# 16.net
KiCad netlist of a schematic drawn in EasyEDA Pro
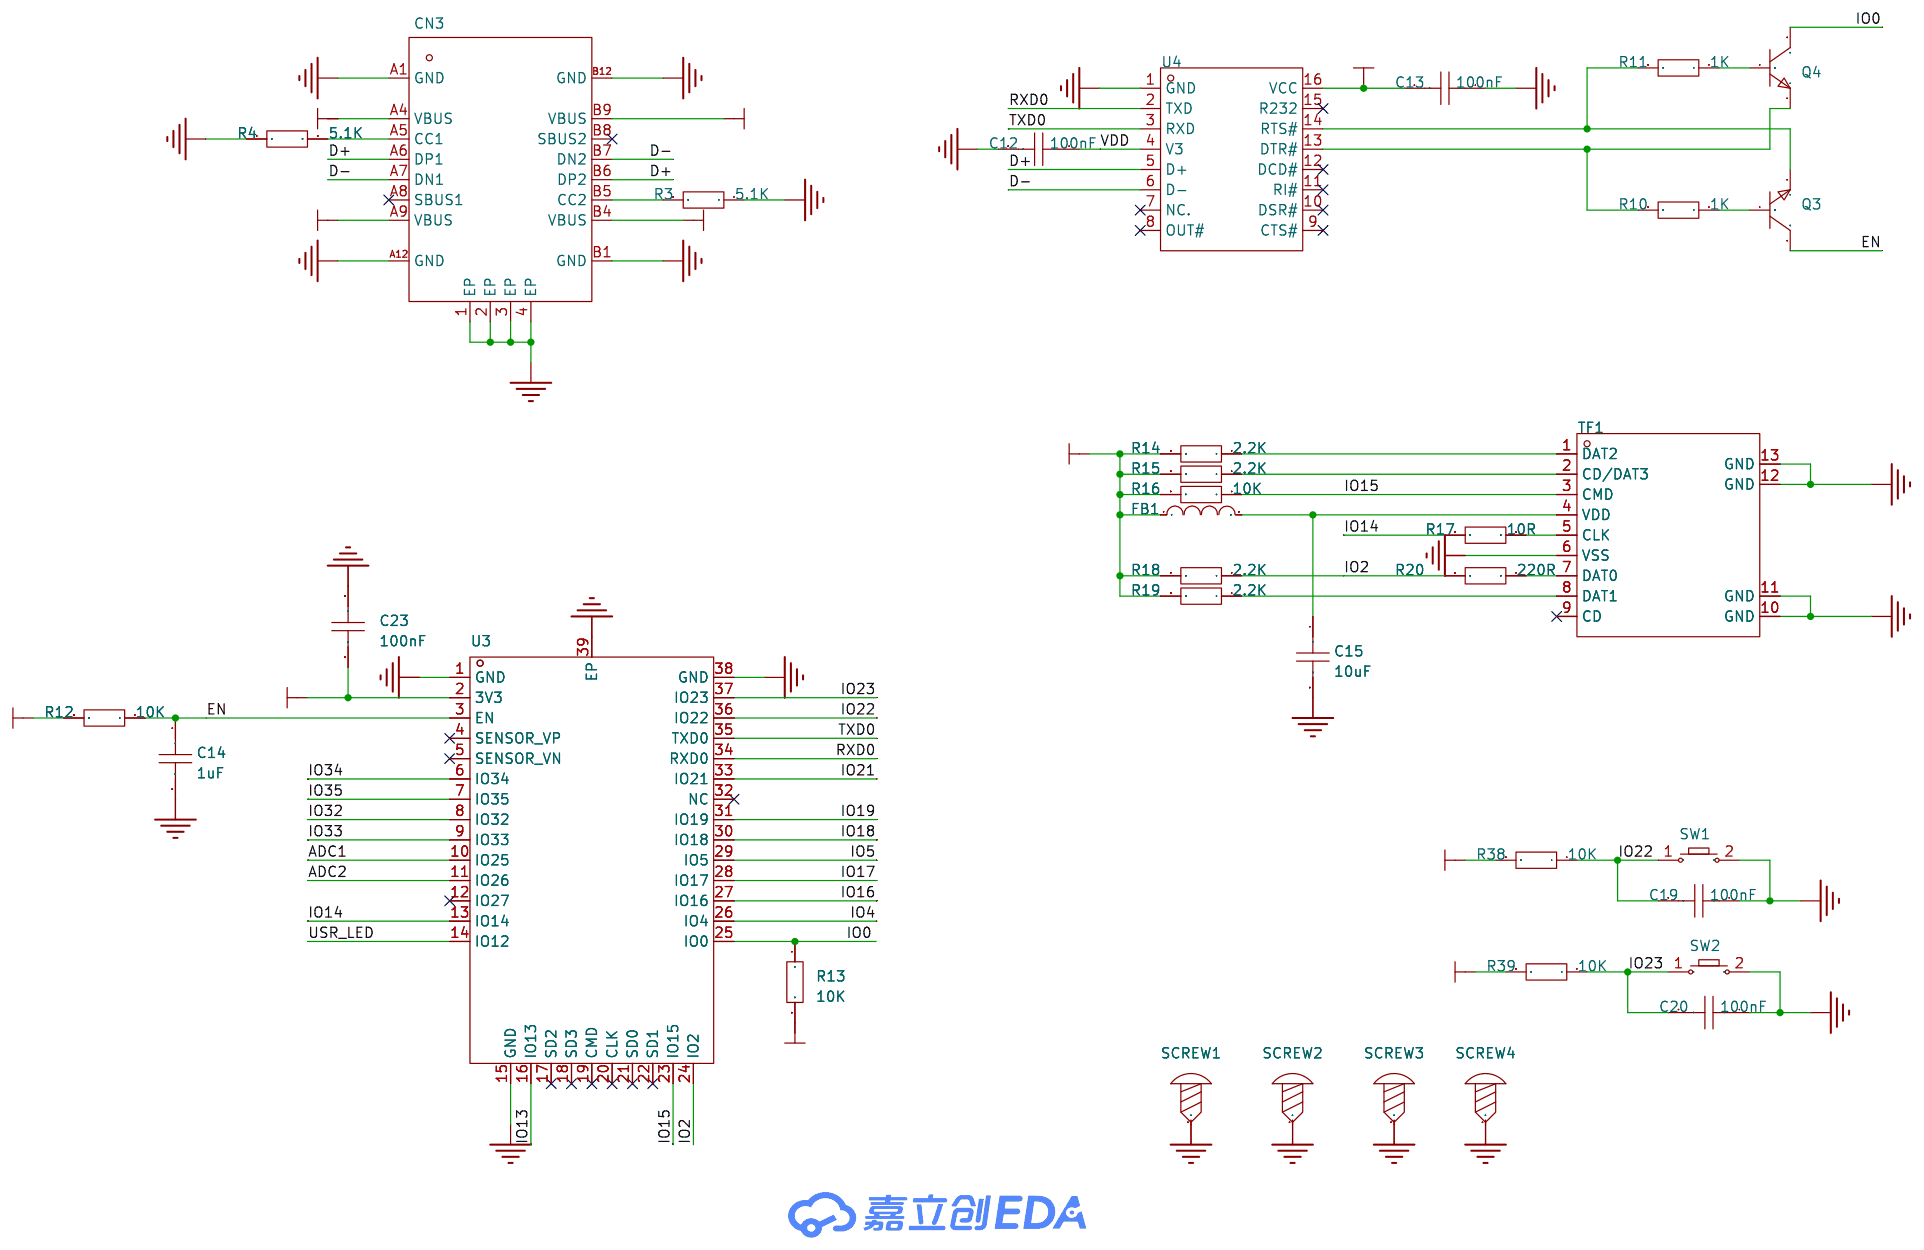
[diagram p0: ESP32]
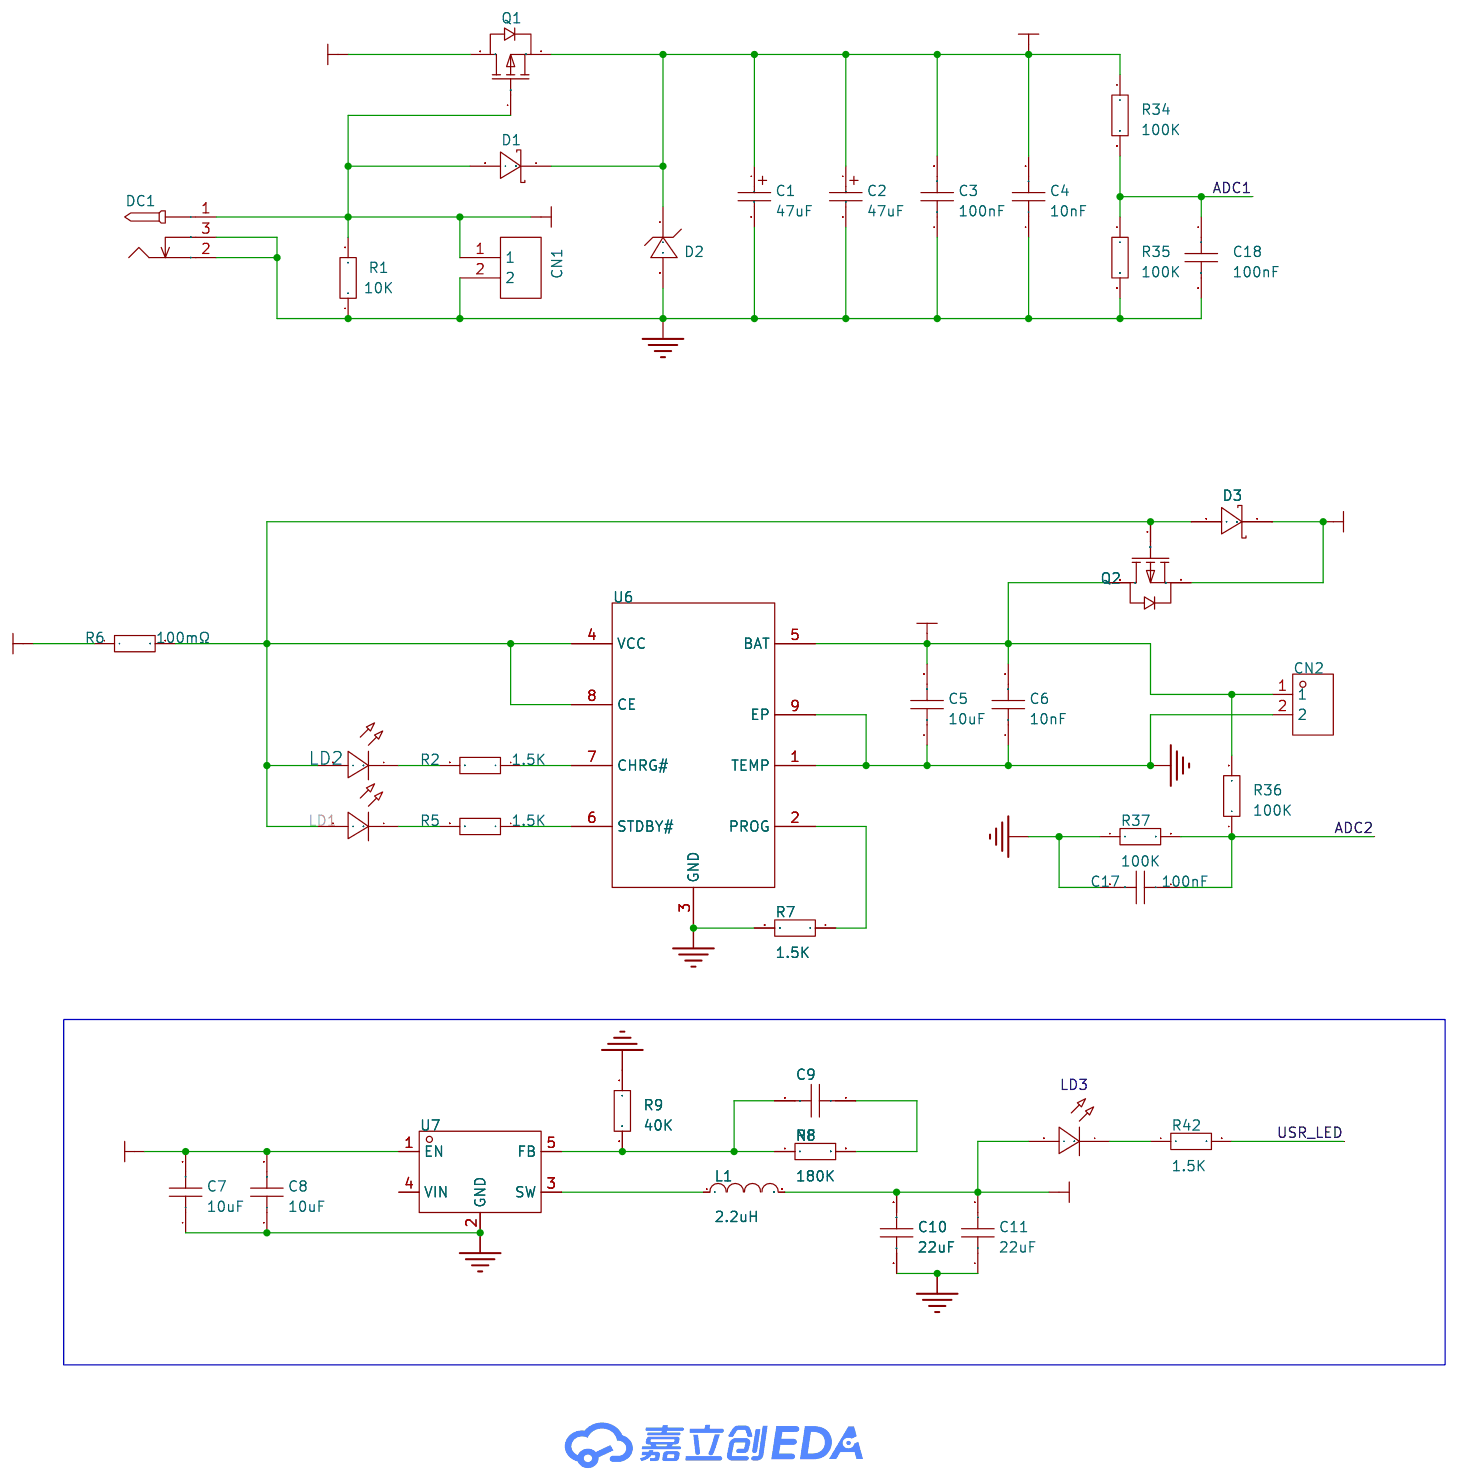
[diagram p1: DC]
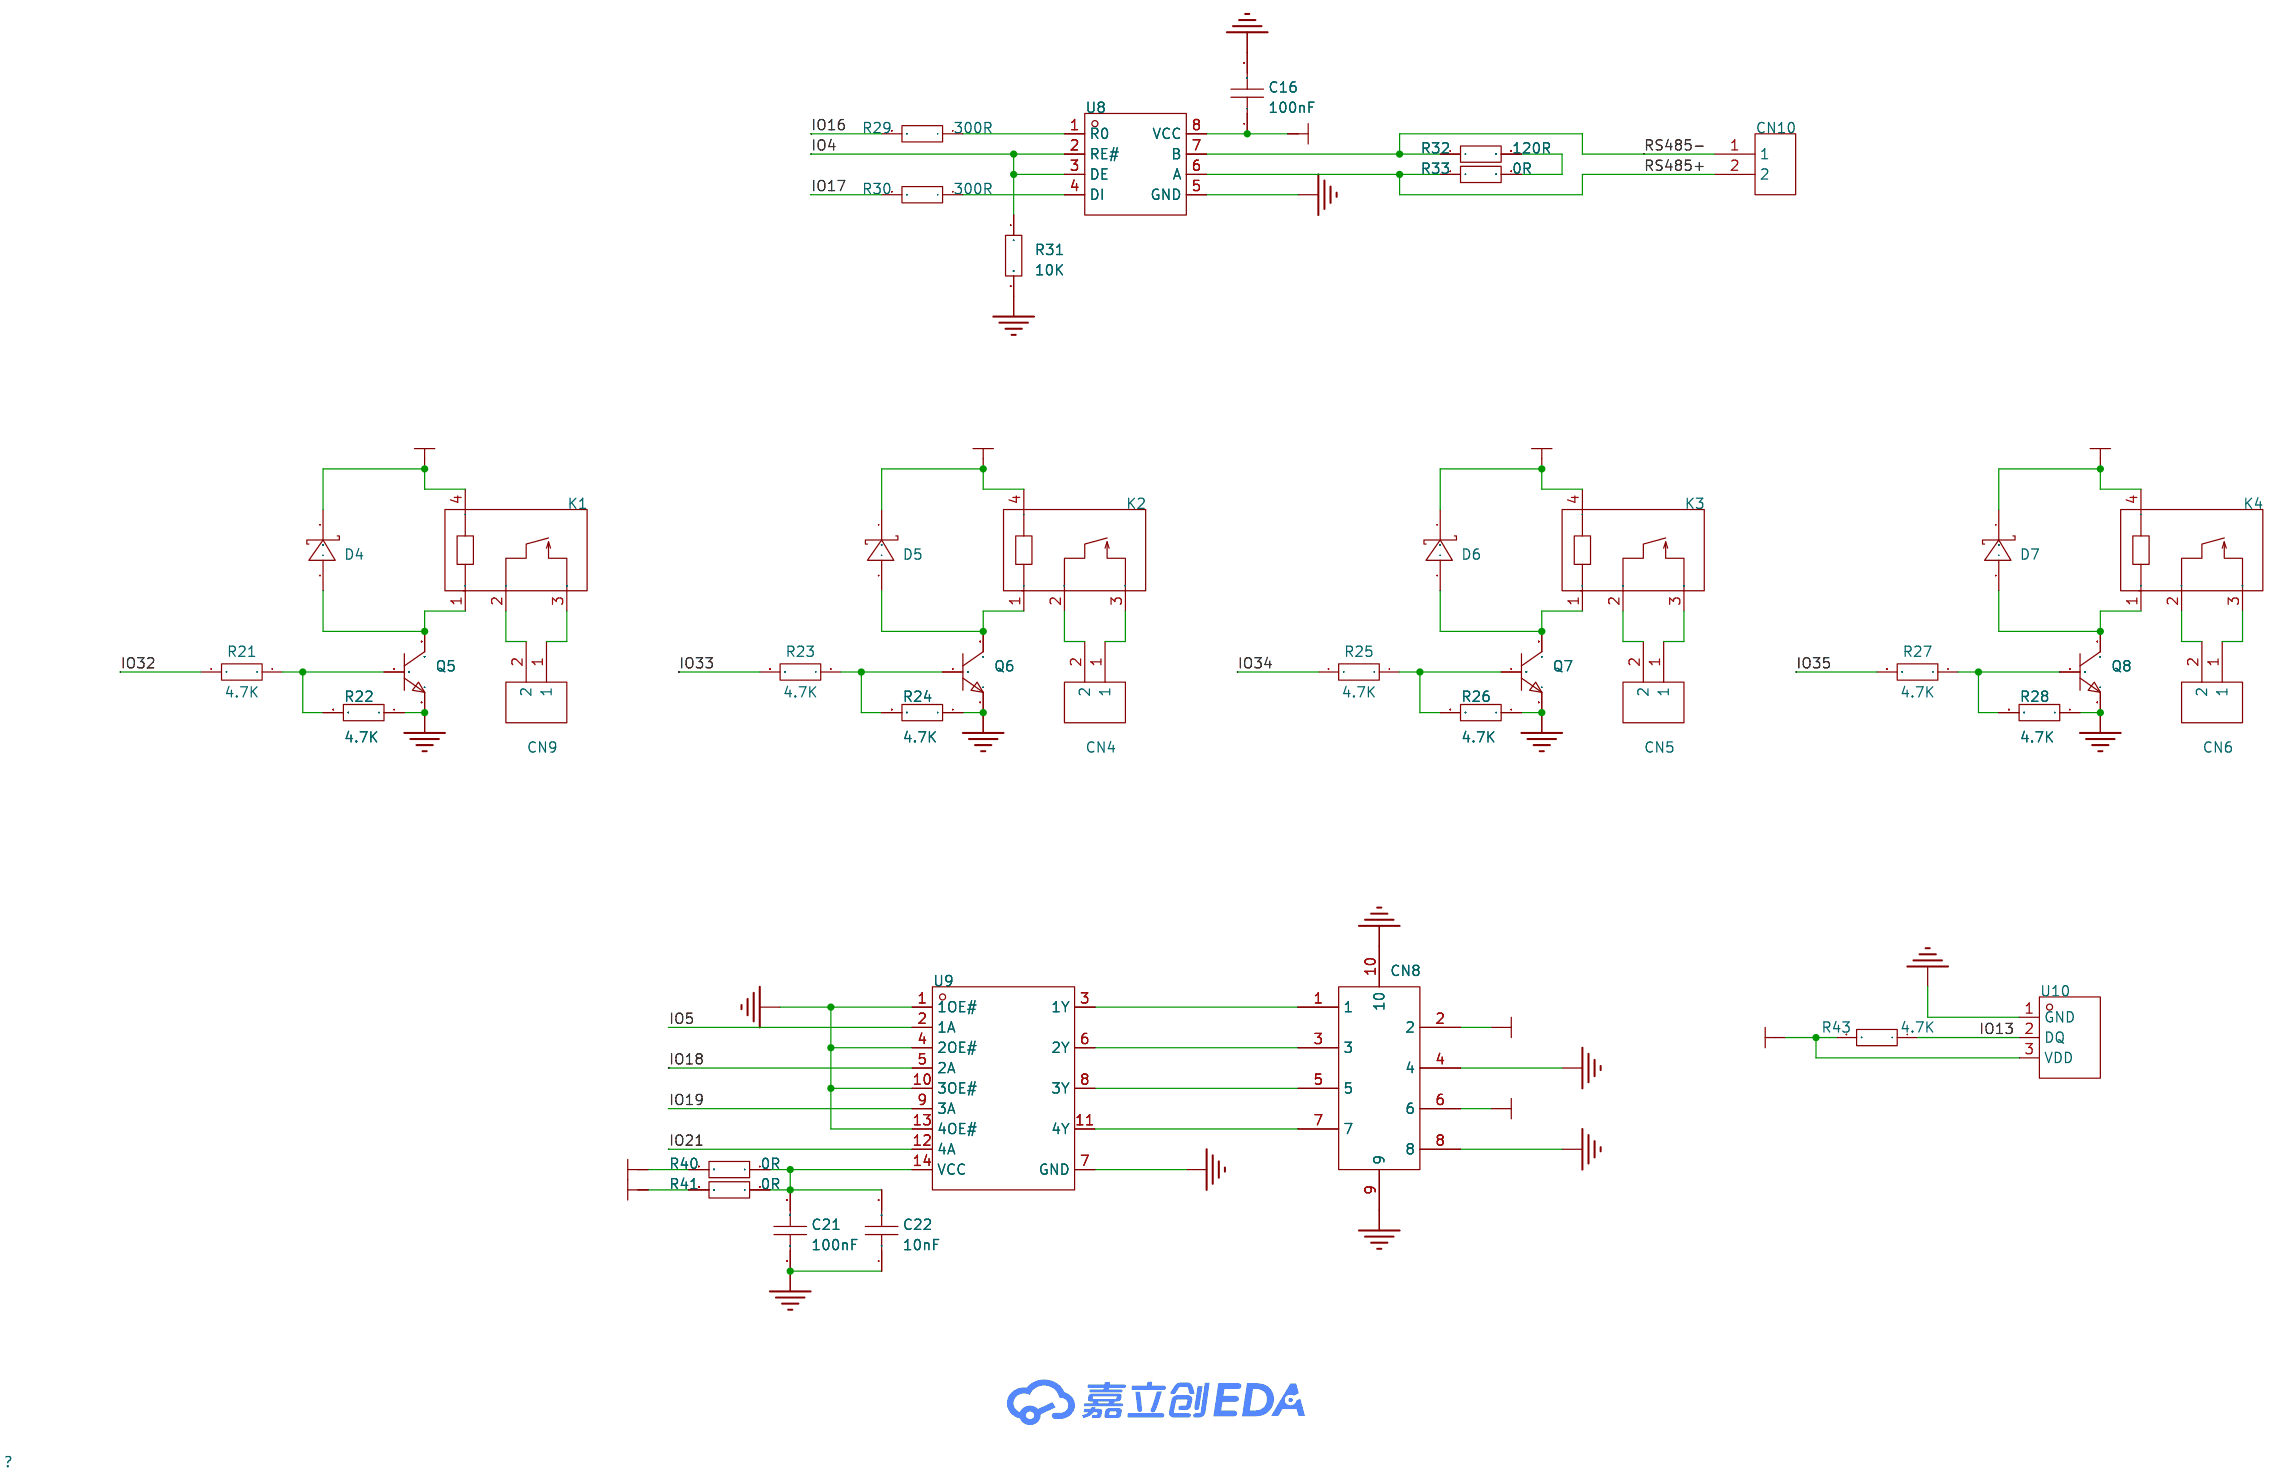
[diagram p2: RELAY]

(export (version "E")
  (design (tool "Eeschema 10.0.6"))
  (components
    (comp (ref "C12")
      (value "100nF")
      (footprint "easyedapro:C0805")
      (libsource (lib "easyedapro") (part "CapAcitance"))
    )
    (comp (ref "C13")
      (value "100nF")
      (footprint "easyedapro:C0805")
      (libsource (lib "easyedapro") (part "CapAcitance"))
    )
    (comp (ref "C14")
      (value "1uF")
      (footprint "easyedapro:C0805")
      (libsource (lib "easyedapro") (part "CapAcitance"))
    )
    (comp (ref "C15")
      (value "10uF")
      (footprint "easyedapro:C0805")
      (libsource (lib "easyedapro") (part "CapAcitance"))
    )
    (comp (ref "C19")
      (value "100nF")
      (footprint "easyedapro:C0805")
      (libsource (lib "easyedapro") (part "CapAcitance"))
    )
    (comp (ref "C20")
      (value "100nF")
      (footprint "easyedapro:C0805")
      (libsource (lib "easyedapro") (part "CapAcitance"))
    )
    (comp (ref "C23")
      (value "100nF")
      (footprint "easyedapro:C0805")
      (libsource (lib "easyedapro") (part "CapAcitance"))
    )
    (comp (ref "CN3")
      (value "~")
      (footprint "easyedapro:USB_TYPE-C-16P")
      (libsource (lib "easyedapro") (part "USB_TYPE-C-16P"))
    )
    (comp (ref "FB1")
      (value "10uH")
      (footprint "easyedapro:L0805")
      (libsource (lib "easyedapro") (part "SDFL2012S100KTF"))
    )
    (comp (ref "Q3")
      (value "SS8050")
      (footprint "easyedapro:SOT-23-3_L2.9-W1.3-P1.90-LS2.4-BR")
      (fields (field (name "Manufacturer") "宏迦橙"))
      (libsource (lib "easyedapro") (part "SS8050_C7420370"))
    )
    (comp (ref "Q4")
      (value "SS8050")
      (footprint "easyedapro:SOT-23-3_L2.9-W1.3-P1.90-LS2.4-BR")
      (fields (field (name "Manufacturer") "宏迦橙"))
      (libsource (lib "easyedapro") (part "SS8050_C7420370"))
    )
    (comp (ref "R3") (value "5.1K") (footprint "easyedapro:R0805") (libsource (lib "easyedapro") (part "电阻")))
    (comp (ref "R4") (value "5.1K") (footprint "easyedapro:R0805") (libsource (lib "easyedapro") (part "电阻")))
    (comp (ref "R10") (value "1K") (footprint "easyedapro:R0805") (libsource (lib "easyedapro") (part "电阻")))
    (comp (ref "R11") (value "1K") (footprint "easyedapro:R0805") (libsource (lib "easyedapro") (part "电阻")))
    (comp (ref "R12") (value "10K") (footprint "easyedapro:R0805") (libsource (lib "easyedapro") (part "电阻")))
    (comp (ref "R13") (value "10K") (footprint "easyedapro:R0805") (libsource (lib "easyedapro") (part "电阻")))
    (comp (ref "R14")
      (value "2.2K")
      (footprint "easyedapro:R0805")
      (libsource (lib "easyedapro") (part "电阻"))
    )
    (comp (ref "R15")
      (value "2.2K")
      (footprint "easyedapro:R0805")
      (libsource (lib "easyedapro") (part "电阻"))
    )
    (comp (ref "R16") (value "10K") (footprint "easyedapro:R0805") (libsource (lib "easyedapro") (part "电阻")))
    (comp (ref "R17") (value "10R") (footprint "easyedapro:R0805") (libsource (lib "easyedapro") (part "电阻")))
    (comp (ref "R18")
      (value "2.2K")
      (footprint "easyedapro:R0805")
      (libsource (lib "easyedapro") (part "电阻"))
    )
    (comp (ref "R19")
      (value "2.2K")
      (footprint "easyedapro:R0805")
      (libsource (lib "easyedapro") (part "电阻"))
    )
    (comp (ref "R20")
      (value "220R")
      (footprint "easyedapro:R0805")
      (libsource (lib "easyedapro") (part "电阻"))
    )
    (comp (ref "R38") (value "10K") (footprint "easyedapro:R0805") (libsource (lib "easyedapro") (part "电阻")))
    (comp (ref "R39") (value "10K") (footprint "easyedapro:R0805") (libsource (lib "easyedapro") (part "电阻")))
    (comp (ref "SCREW1")
      (value "~")
      (footprint "easyedapro:M2螺丝")
      (libsource (lib "easyedapro") (part "螺丝孔"))
    )
    (comp (ref "SCREW2")
      (value "~")
      (footprint "easyedapro:M2螺丝")
      (libsource (lib "easyedapro") (part "螺丝孔"))
    )
    (comp (ref "SCREW3")
      (value "~")
      (footprint "easyedapro:M2螺丝")
      (libsource (lib "easyedapro") (part "螺丝孔"))
    )
    (comp (ref "SCREW4")
      (value "~")
      (footprint "easyedapro:M2螺丝")
      (libsource (lib "easyedapro") (part "螺丝孔"))
    )
    (comp (ref "SW1")
      (value "~")
      (footprint "easyedapro:Key_SMD_3x4x2")
      (libsource (lib "easyedapro") (part "轻触按键x2"))
    )
    (comp (ref "SW2")
      (value "~")
      (footprint "easyedapro:Key_SMD_3x4x2")
      (libsource (lib "easyedapro") (part "轻触按键x2"))
    )
    (comp (ref "TF1")
      (value "TF-CARD H1.8")
      (footprint "easyedapro:TF-SMD_TF-CARD-H1.8")
      (fields (field (name "Manufacturer") "SHOU HAN(首韩)"))
      (libsource (lib "easyedapro") (part "TF-CARD H1.8"))
    )
    (comp (ref "U3")
      (value "ESP32-WROOM-32")
      (footprint "easyedapro:WIFIM-SMD_ESP-WROOM-32")
      (fields (field (name "Manufacturer") "ESPRESSIF(乐鑫)"))
      (libsource (lib "easyedapro") (part "ESP-WROOM-32"))
    )
    (comp (ref "U4")
      (value "CH340C")
      (footprint "easyedapro:SOP-16_L10.0-W3.9-P1.27-LS6.0-BL")
      (fields (field (name "Manufacturer") "WCH(南京沁恒)"))
      (libsource (lib "easyedapro") (part "CH340C"))
    )
    (comp (ref "C1")
      (value "47uF")
      (footprint "easyedapro:C_Ele_SMD_4x5.5mm")
      (libsource (lib "easyedapro") (part "CAP"))
    )
    (comp (ref "C2")
      (value "47uF")
      (footprint "easyedapro:C_Ele_SMD_4x5.5mm")
      (libsource (lib "easyedapro") (part "CAP"))
    )
    (comp (ref "C3")
      (value "100nF")
      (footprint "easyedapro:C0805")
      (libsource (lib "easyedapro") (part "CapAcitance"))
    )
    (comp (ref "C4")
      (value "10nF")
      (footprint "easyedapro:C0805")
      (libsource (lib "easyedapro") (part "CapAcitance"))
    )
    (comp (ref "C5")
      (value "10uF")
      (footprint "easyedapro:C0805")
      (libsource (lib "easyedapro") (part "CapAcitance"))
    )
    (comp (ref "C6")
      (value "10nF")
      (footprint "easyedapro:C0805")
      (libsource (lib "easyedapro") (part "CapAcitance"))
    )
    (comp (ref "C7")
      (value "10uF")
      (footprint "easyedapro:C0805")
      (libsource (lib "easyedapro") (part "CapAcitance"))
    )
    (comp (ref "C8")
      (value "10uF")
      (footprint "easyedapro:C0805")
      (libsource (lib "easyedapro") (part "CapAcitance"))
    )
    (comp (ref "C9")
      (value "NF")
      (footprint "easyedapro:C0805")
      (libsource (lib "easyedapro") (part "CapAcitance"))
    )
    (comp (ref "C10")
      (value "22uF")
      (footprint "easyedapro:C0805")
      (libsource (lib "easyedapro") (part "CapAcitance"))
    )
    (comp (ref "C11")
      (value "22uF")
      (footprint "easyedapro:C0805")
      (libsource (lib "easyedapro") (part "CapAcitance"))
    )
    (comp (ref "C17")
      (value "100nF")
      (footprint "easyedapro:C0805")
      (libsource (lib "easyedapro") (part "CapAcitance"))
    )
    (comp (ref "C18")
      (value "100nF")
      (footprint "easyedapro:C0805")
      (libsource (lib "easyedapro") (part "CapAcitance"))
    )
    (comp (ref "CN1")
      (value "WJ500V-5.08-2P")
      (footprint "easyedapro:CONN-TH_2P-P5.00_WJ500V-5.08-2P")
      (fields (field (name "Manufacturer") "KANGNEX(康奈克斯电气)"))
      (libsource (lib "easyedapro") (part "WJ500V-5.08-2P-14-00A"))
    )
    (comp (ref "CN2")
      (value "ZX-XH2.54-2PZZ")
      (footprint "easyedapro:CONN-TH_2P-P2.50_HX25003-2A")
      (fields (field (name "Manufacturer") "Megastar(兆星)"))
      (libsource (lib "easyedapro") (part "ZX-XH2.54-2PZZ"))
    )
    (comp (ref "D1")
      (value "SS34")
      (footprint "easyedapro:SMC_L6.9-W5.9-LS7.9-RD")
      (fields (field (name "Manufacturer") "onsemi(安森美)"))
      (libsource (lib "easyedapro") (part "SS34_C154551"))
    )
    (comp (ref "D2")
      (value "SMBJ6.0A")
      (footprint "easyedapro:SMB_L4.6-W3.6-LS5.3-RD")
      (fields (field (name "Manufacturer") "RUILON(瑞隆源)"))
      (libsource (lib "easyedapro") (part "SMBJ6.0A_C2987966"))
    )
    (comp (ref "D3")
      (value "SS34")
      (footprint "easyedapro:SMC_L6.9-W5.9-LS7.9-RD")
      (fields (field (name "Manufacturer") "onsemi(安森美)"))
      (libsource (lib "easyedapro") (part "SS34_C154551"))
    )
    (comp (ref "DC1")
      (value "~")
      (footprint "easyedapro:DC-005_2.5")
      (libsource (lib "easyedapro") (part "DC-005_2.5"))
    )
    (comp (ref "L1")
      (value "2.2uH")
      (footprint "easyedapro:IND-SMD_L4.4-W4.2")
      (fields (field (name "Manufacturer Part") "FXL0420-2R2-M") (field (name "Manufacturer") "cjiang(长江微电)"))
      (libsource (lib "easyedapro") (part "FXL0420-2R2-M"))
    )
    (comp (ref "LD1")
      (value "~")
      (footprint "easyedapro:LED_0805")
      (libsource (lib "easyedapro") (part "LED_G"))
    )
    (comp (ref "LD2")
      (value "~")
      (footprint "easyedapro:LED_0805")
      (libsource (lib "easyedapro") (part "LED_R"))
    )
    (comp (ref "LD3")
      (value "~")
      (footprint "easyedapro:LED_0805")
      (libsource (lib "easyedapro") (part "LED_B"))
    )
    (comp (ref "Q1")
      (value "AO3401A")
      (footprint "easyedapro:SOT-23_L2.9-W1.3-P1.90-LS2.4-BR")
      (fields (field (name "Manufacturer") "AOS"))
      (libsource (lib "easyedapro") (part "AO3401A"))
    )
    (comp (ref "Q2")
      (value "AO3401A")
      (footprint "easyedapro:SOT-23_L2.9-W1.3-P1.90-LS2.4-BR")
      (fields (field (name "Manufacturer") "AOS"))
      (libsource (lib "easyedapro") (part "AO3401A"))
    )
    (comp (ref "R1") (value "10K") (footprint "easyedapro:R0805") (libsource (lib "easyedapro") (part "电阻")))
    (comp (ref "R2") (value "1.5K") (footprint "easyedapro:R0805") (libsource (lib "easyedapro") (part "电阻")))
    (comp (ref "R5") (value "1.5K") (footprint "easyedapro:R0805") (libsource (lib "easyedapro") (part "电阻")))
    (comp (ref "R6")
      (value "100mΩ")
      (footprint "easyedapro:R1210")
      (fields
        (field (name "Manufacturer Part") "1210W2F100LT5E")
        (field (name "Manufacturer") "UNI-ROYAL(厚声)")
      )
      (libsource (lib "easyedapro") (part "1210W2F100LT5E"))
    )
    (comp (ref "R7") (value "1.5K") (footprint "easyedapro:R0805") (libsource (lib "easyedapro") (part "电阻")))
    (comp (ref "R8") (value "180K") (footprint "easyedapro:R0805") (libsource (lib "easyedapro") (part "电阻")))
    (comp (ref "R9") (value "40K") (footprint "easyedapro:R0805") (libsource (lib "easyedapro") (part "电阻")))
    (comp (ref "R34")
      (value "100K")
      (footprint "easyedapro:R0805")
      (libsource (lib "easyedapro") (part "电阻"))
    )
    (comp (ref "R35")
      (value "100K")
      (footprint "easyedapro:R0805")
      (libsource (lib "easyedapro") (part "电阻"))
    )
    (comp (ref "R36")
      (value "100K")
      (footprint "easyedapro:R0805")
      (libsource (lib "easyedapro") (part "电阻"))
    )
    (comp (ref "R37")
      (value "100K")
      (footprint "easyedapro:R0805")
      (libsource (lib "easyedapro") (part "电阻"))
    )
    (comp (ref "R42")
      (value "1.5K")
      (footprint "easyedapro:R0805")
      (libsource (lib "easyedapro") (part "电阻"))
    )
    (comp (ref "U6")
      (value "TP4056-42-ESOP8")
      (footprint "easyedapro:ESOP-8_L4.9-W3.9-P1.27-LS6.0-BL-EP")
      (fields (field (name "Manufacturer") "TOPPOWER(南京拓微)"))
      (libsource (lib "easyedapro") (part "TP4056"))
    )
    (comp (ref "U7") (value "~") (libsource (lib "easyedapro") (part "XDC")))
    (comp (ref "C16")
      (value "100nF")
      (footprint "easyedapro:C0805")
      (libsource (lib "easyedapro") (part "CapAcitance"))
    )
    (comp (ref "C21")
      (value "100nF")
      (footprint "easyedapro:C0805")
      (libsource (lib "easyedapro") (part "CapAcitance"))
    )
    (comp (ref "C22")
      (value "10nF")
      (footprint "easyedapro:C0805")
      (libsource (lib "easyedapro") (part "CapAcitance"))
    )
    (comp (ref "CN4")
      (value "WJ500V-5.08-2P")
      (footprint "easyedapro:CONN-TH_2P-P5.00_WJ500V-5.08-2P")
      (fields (field (name "Manufacturer") "KANGNEX(康奈克斯电气)"))
      (libsource (lib "easyedapro") (part "WJ500V-5.08-2P-14-00A"))
    )
    (comp (ref "CN5")
      (value "WJ500V-5.08-2P")
      (footprint "easyedapro:CONN-TH_2P-P5.00_WJ500V-5.08-2P")
      (fields (field (name "Manufacturer") "KANGNEX(康奈克斯电气)"))
      (libsource (lib "easyedapro") (part "WJ500V-5.08-2P-14-00A"))
    )
    (comp (ref "CN6")
      (value "WJ500V-5.08-2P")
      (footprint "easyedapro:CONN-TH_2P-P5.00_WJ500V-5.08-2P")
      (fields (field (name "Manufacturer") "KANGNEX(康奈克斯电气)"))
      (libsource (lib "easyedapro") (part "WJ500V-5.08-2P-14-00A"))
    )
    (comp (ref "CN8")
      (value "8P-立贴带锁")
      (footprint "easyedapro:FPC-SMD_8P-P0.50_AFC11-S08ICC-00")
      (libsource (lib "easyedapro") (part "8P-立贴带锁"))
    )
    (comp (ref "CN9")
      (value "WJ500V-5.08-2P")
      (footprint "easyedapro:CONN-TH_2P-P5.00_WJ500V-5.08-2P")
      (fields (field (name "Manufacturer") "KANGNEX(康奈克斯电气)"))
      (libsource (lib "easyedapro") (part "WJ500V-5.08-2P-14-00A"))
    )
    (comp (ref "CN10")
      (value "WJ500V-5.08-2P")
      (footprint "easyedapro:CONN-TH_2P-P5.00_WJ500V-5.08-2P")
      (fields (field (name "Manufacturer") "KANGNEX(康奈克斯电气)"))
      (libsource (lib "easyedapro") (part "WJ500V-5.08-2P-14-00A"))
    )
    (comp (ref "D4")
      (value "SS34")
      (footprint "easyedapro:SMC_L6.9-W5.9-LS7.9-RD")
      (fields (field (name "Manufacturer") "onsemi(安森美)"))
      (libsource (lib "easyedapro") (part "SS34_C154551"))
    )
    (comp (ref "D5")
      (value "SS34")
      (footprint "easyedapro:SMC_L6.9-W5.9-LS7.9-RD")
      (fields (field (name "Manufacturer") "onsemi(安森美)"))
      (libsource (lib "easyedapro") (part "SS34_C154551"))
    )
    (comp (ref "D6")
      (value "SS34")
      (footprint "easyedapro:SMC_L6.9-W5.9-LS7.9-RD")
      (fields (field (name "Manufacturer") "onsemi(安森美)"))
      (libsource (lib "easyedapro") (part "SS34_C154551"))
    )
    (comp (ref "D7")
      (value "SS34")
      (footprint "easyedapro:SMC_L6.9-W5.9-LS7.9-RD")
      (fields (field (name "Manufacturer") "onsemi(安森美)"))
      (libsource (lib "easyedapro") (part "SS34_C154551"))
    )
    (comp (ref "K1")
      (value "G5NB-1A-E-12VDC")
      (footprint "easyedapro:RELAY-TH_G5NB-1A-E-DCXX")
      (libsource (lib "easyedapro") (part "G5NB-1A-E-12VDC"))
    )
    (comp (ref "K2")
      (value "G5NB-1A-E-12VDC")
      (footprint "easyedapro:RELAY-TH_G5NB-1A-E-DCXX")
      (libsource (lib "easyedapro") (part "G5NB-1A-E-12VDC"))
    )
    (comp (ref "K3")
      (value "G5NB-1A-E-12VDC")
      (footprint "easyedapro:RELAY-TH_G5NB-1A-E-DCXX")
      (libsource (lib "easyedapro") (part "G5NB-1A-E-12VDC"))
    )
    (comp (ref "K4")
      (value "G5NB-1A-E-12VDC")
      (footprint "easyedapro:RELAY-TH_G5NB-1A-E-DCXX")
      (libsource (lib "easyedapro") (part "G5NB-1A-E-12VDC"))
    )
    (comp (ref "Q5")
      (value "SS8050")
      (footprint "easyedapro:SOT-23-3_L2.9-W1.3-P1.90-LS2.4-BR")
      (fields (field (name "Manufacturer") "宏迦橙"))
      (libsource (lib "easyedapro") (part "SS8050_C7420370"))
    )
    (comp (ref "Q6")
      (value "SS8050")
      (footprint "easyedapro:SOT-23-3_L2.9-W1.3-P1.90-LS2.4-BR")
      (fields (field (name "Manufacturer") "宏迦橙"))
      (libsource (lib "easyedapro") (part "SS8050_C7420370"))
    )
    (comp (ref "Q7")
      (value "SS8050")
      (footprint "easyedapro:SOT-23-3_L2.9-W1.3-P1.90-LS2.4-BR")
      (fields (field (name "Manufacturer") "宏迦橙"))
      (libsource (lib "easyedapro") (part "SS8050_C7420370"))
    )
    (comp (ref "Q8")
      (value "SS8050")
      (footprint "easyedapro:SOT-23-3_L2.9-W1.3-P1.90-LS2.4-BR")
      (fields (field (name "Manufacturer") "宏迦橙"))
      (libsource (lib "easyedapro") (part "SS8050_C7420370"))
    )
    (comp (ref "R21")
      (value "4.7K")
      (footprint "easyedapro:R0805")
      (libsource (lib "easyedapro") (part "电阻"))
    )
    (comp (ref "R22")
      (value "4.7K")
      (footprint "easyedapro:R0805")
      (libsource (lib "easyedapro") (part "电阻"))
    )
    (comp (ref "R23")
      (value "4.7K")
      (footprint "easyedapro:R0805")
      (libsource (lib "easyedapro") (part "电阻"))
    )
    (comp (ref "R24")
      (value "4.7K")
      (footprint "easyedapro:R0805")
      (libsource (lib "easyedapro") (part "电阻"))
    )
    (comp (ref "R25")
      (value "4.7K")
      (footprint "easyedapro:R0805")
      (libsource (lib "easyedapro") (part "电阻"))
    )
    (comp (ref "R26")
      (value "4.7K")
      (footprint "easyedapro:R0805")
      (libsource (lib "easyedapro") (part "电阻"))
    )
    (comp (ref "R27")
      (value "4.7K")
      (footprint "easyedapro:R0805")
      (libsource (lib "easyedapro") (part "电阻"))
    )
    (comp (ref "R28")
      (value "4.7K")
      (footprint "easyedapro:R0805")
      (libsource (lib "easyedapro") (part "电阻"))
    )
    (comp (ref "R29")
      (value "300R")
      (footprint "easyedapro:R0805")
      (libsource (lib "easyedapro") (part "电阻"))
    )
    (comp (ref "R30")
      (value "300R")
      (footprint "easyedapro:R0805")
      (libsource (lib "easyedapro") (part "电阻"))
    )
    (comp (ref "R31") (value "10K") (footprint "easyedapro:R0805") (libsource (lib "easyedapro") (part "电阻")))
    (comp (ref "R32")
      (value "120R")
      (footprint "easyedapro:R0805")
      (libsource (lib "easyedapro") (part "电阻"))
    )
    (comp (ref "R33") (value "0R") (footprint "easyedapro:R0805") (libsource (lib "easyedapro") (part "电阻")))
    (comp (ref "R40") (value "0R") (footprint "easyedapro:R0805") (libsource (lib "easyedapro") (part "电阻")))
    (comp (ref "R41") (value "0R") (footprint "easyedapro:R0805") (libsource (lib "easyedapro") (part "电阻")))
    (comp (ref "R43")
      (value "4.7K")
      (footprint "easyedapro:R0805")
      (libsource (lib "easyedapro") (part "电阻"))
    )
    (comp (ref "U8")
      (value "MAX485EIM/TR")
      (footprint "easyedapro:SOP-8_L4.9-W3.9-P1.27-LS6.0-BL")
      (fields (field (name "Manufacturer") "HGSEMI(华冠)"))
      (libsource (lib "easyedapro") (part "MAX485EIM/TR"))
    )
    (comp (ref "U9")
      (value "74HC125D/S400118")
      (footprint "easyedapro:SOIC-14_L8.6-W3.8-P1.27-LS6.0-BL")
      (fields (field (name "Manufacturer") "Nexperia(安世)"))
      (libsource (lib "easyedapro") (part "74HC125D/S400118"))
    )
    (comp (ref "U10")
      (value "GX18B20")
      (footprint "easyedapro:TO-92-3_L4.9-W3.7-P1.27-L")
      (fields (field (name "Manufacturer") "GXCAS(中科银河芯)"))
      (libsource (lib "easyedapro") (part "GX18B20"))
    )
  )
  (nets
    (net (code "1") (name "ADC1") (class "Default")
      (node (ref "C18") (pin "1") (pinfunction "1_1") (pintype "input"))
      (node (ref "R34") (pin "2") (pinfunction "2_2") (pintype "input"))
      (node (ref "R35") (pin "1") (pinfunction "1_1") (pintype "input"))
      (node (ref "U3") (pin "10") (pinfunction "IO25_10") (pintype "unspecified"))
    )
    (net (code "2") (name "ADC2") (class "Default")
      (node (ref "C17") (pin "1") (pinfunction "1_1") (pintype "input"))
      (node (ref "R36") (pin "1") (pinfunction "1_1") (pintype "input"))
      (node (ref "R37") (pin "2") (pinfunction "2_2") (pintype "input"))
      (node (ref "U3") (pin "11") (pinfunction "IO26_11") (pintype "unspecified"))
    )
    (net (code "3") (name "D+") (class "Default")
      (node (ref "CN3") (pin "A6") (pinfunction "DP1_A6") (pintype "input"))
      (node (ref "CN3") (pin "B6") (pinfunction "DP2_B6") (pintype "input"))
      (node (ref "U4") (pin "5") (pinfunction "D+_5") (pintype "unspecified"))
    )
    (net (code "4") (name "D-") (class "Default")
      (node (ref "CN3") (pin "A7") (pinfunction "DN1_A7") (pintype "input"))
      (node (ref "CN3") (pin "B7") (pinfunction "DN2_B7") (pintype "input"))
      (node (ref "U4") (pin "6") (pinfunction "D-_6") (pintype "unspecified"))
    )
    (net (code "5") (name "EN") (class "Default")
      (node (ref "C14") (pin "1") (pinfunction "1_1") (pintype "input"))
      (node (ref "Q3") (pin "3") (pinfunction "C_3") (pintype "input"))
      (node (ref "R12") (pin "1") (pinfunction "1_1") (pintype "input"))
      (node (ref "U3") (pin "3") (pinfunction "EN_3") (pintype "unspecified"))
    )
    (net (code "6") (name "GND") (class "Default")
      (node (ref "C1") (pin "2") (pinfunction "2_2") (pintype "input"))
      (node (ref "C10") (pin "1") (pinfunction "1_1") (pintype "input"))
      (node (ref "C11") (pin "1") (pinfunction "1_1") (pintype "input"))
      (node (ref "C12") (pin "2") (pinfunction "2_2") (pintype "input"))
      (node (ref "C13") (pin "1") (pinfunction "1_1") (pintype "input"))
      (node (ref "C14") (pin "2") (pinfunction "2_2") (pintype "input"))
      (node (ref "C15") (pin "2") (pinfunction "2_2") (pintype "input"))
      (node (ref "C16") (pin "2") (pinfunction "2_2") (pintype "input"))
      (node (ref "C17") (pin "2") (pinfunction "2_2") (pintype "input"))
      (node (ref "C18") (pin "2") (pinfunction "2_2") (pintype "input"))
      (node (ref "C19") (pin "1") (pinfunction "1_1") (pintype "input"))
      (node (ref "C2") (pin "2") (pinfunction "2_2") (pintype "input"))
      (node (ref "C20") (pin "1") (pinfunction "1_1") (pintype "input"))
      (node (ref "C21") (pin "1") (pinfunction "1_1") (pintype "input"))
      (node (ref "C22") (pin "1") (pinfunction "1_1") (pintype "input"))
      (node (ref "C23") (pin "2") (pinfunction "2_2") (pintype "input"))
      (node (ref "C3") (pin "1") (pinfunction "1_1") (pintype "input"))
      (node (ref "C4") (pin "1") (pinfunction "1_1") (pintype "input"))
      (node (ref "C5") (pin "1") (pinfunction "1_1") (pintype "input"))
      (node (ref "C6") (pin "1") (pinfunction "1_1") (pintype "input"))
      (node (ref "C7") (pin "1") (pinfunction "1_1") (pintype "input"))
      (node (ref "C8") (pin "1") (pinfunction "1_1") (pintype "input"))
      (node (ref "CN1") (pin "2") (pinfunction "2_2") (pintype "unspecified"))
      (node (ref "CN2") (pin "2") (pinfunction "2_2") (pintype "unspecified"))
      (node (ref "CN3") (pin "1") (pinfunction "EP_1") (pintype "input"))
      (node (ref "CN3") (pin "2") (pinfunction "EP_2") (pintype "input"))
      (node (ref "CN3") (pin "3") (pinfunction "EP_3") (pintype "input"))
      (node (ref "CN3") (pin "4") (pinfunction "EP_4") (pintype "input"))
      (node (ref "CN3") (pin "A1") (pinfunction "GND_A1") (pintype "input"))
      (node (ref "CN3") (pin "A12") (pinfunction "GND_A12") (pintype "input"))
      (node (ref "CN3") (pin "B1") (pinfunction "GND_B1") (pintype "input"))
      (node (ref "CN3") (pin "B12") (pinfunction "GND_B12") (pintype "input"))
      (node (ref "CN8") (pin "10") (pinfunction "10_10") (pintype "unspecified"))
      (node (ref "CN8") (pin "4") (pinfunction "4_4") (pintype "unspecified"))
      (node (ref "CN8") (pin "8") (pinfunction "8_8") (pintype "unspecified"))
      (node (ref "CN8") (pin "9") (pinfunction "9_9") (pintype "unspecified"))
      (node (ref "D2") (pin "2") (pinfunction "2_2") (pintype "unspecified"))
      (node (ref "DC1") (pin "2") (pinfunction "2_2") (pintype "input"))
      (node (ref "DC1") (pin "3") (pinfunction "3_3") (pintype "input"))
      (node (ref "Q5") (pin "2") (pinfunction "E_2") (pintype "input"))
      (node (ref "Q6") (pin "2") (pinfunction "E_2") (pintype "input"))
      (node (ref "Q7") (pin "2") (pinfunction "E_2") (pintype "input"))
      (node (ref "Q8") (pin "2") (pinfunction "E_2") (pintype "input"))
      (node (ref "R1") (pin "1") (pinfunction "1_1") (pintype "input"))
      (node (ref "R22") (pin "1") (pinfunction "1_1") (pintype "input"))
      (node (ref "R24") (pin "1") (pinfunction "1_1") (pintype "input"))
      (node (ref "R26") (pin "1") (pinfunction "1_1") (pintype "input"))
      (node (ref "R28") (pin "1") (pinfunction "1_1") (pintype "input"))
      (node (ref "R3") (pin "1") (pinfunction "1_1") (pintype "input"))
      (node (ref "R31") (pin "2") (pinfunction "2_2") (pintype "input"))
      (node (ref "R35") (pin "2") (pinfunction "2_2") (pintype "input"))
      (node (ref "R37") (pin "1") (pinfunction "1_1") (pintype "input"))
      (node (ref "R4") (pin "1") (pinfunction "1_1") (pintype "input"))
      (node (ref "R7") (pin "2") (pinfunction "2_2") (pintype "input"))
      (node (ref "R9") (pin "1") (pinfunction "1_1") (pintype "input"))
      (node (ref "SCREW1") (pin "1") (pinfunction "1_1") (pintype "input"))
      (node (ref "SCREW2") (pin "1") (pinfunction "1_1") (pintype "input"))
      (node (ref "SCREW3") (pin "1") (pinfunction "1_1") (pintype "input"))
      (node (ref "SCREW4") (pin "1") (pinfunction "1_1") (pintype "input"))
      (node (ref "SW1") (pin "2") (pinfunction "2_2") (pintype "input"))
      (node (ref "SW2") (pin "2") (pinfunction "2_2") (pintype "input"))
      (node (ref "TF1") (pin "10") (pinfunction "GND_10") (pintype "unspecified"))
      (node (ref "TF1") (pin "11") (pinfunction "GND_11") (pintype "unspecified"))
      (node (ref "TF1") (pin "12") (pinfunction "GND_12") (pintype "unspecified"))
      (node (ref "TF1") (pin "13") (pinfunction "GND_13") (pintype "unspecified"))
      (node (ref "TF1") (pin "6") (pinfunction "VSS_6") (pintype "unspecified"))
      (node (ref "U10") (pin "1") (pinfunction "GND_1") (pintype "input"))
      (node (ref "U3") (pin "1") (pinfunction "GND_1") (pintype "unspecified"))
      (node (ref "U3") (pin "15") (pinfunction "GND_15") (pintype "unspecified"))
      (node (ref "U3") (pin "38") (pinfunction "GND_38") (pintype "unspecified"))
      (node (ref "U3") (pin "39") (pinfunction "EP_39") (pintype "unspecified"))
      (node (ref "U4") (pin "1") (pinfunction "GND_1") (pintype "unspecified"))
      (node (ref "U6") (pin "1") (pinfunction "TEMP_1") (pintype "unspecified"))
      (node (ref "U6") (pin "3") (pinfunction "GND_3") (pintype "unspecified"))
      (node (ref "U6") (pin "9") (pinfunction "EP_9") (pintype "unspecified"))
      (node (ref "U7") (pin "2") (pinfunction "GND_2") (pintype "input"))
      (node (ref "U8") (pin "5") (pinfunction "GND_5") (pintype "unspecified"))
      (node (ref "U9") (pin "1") (pinfunction "1OE#_1") (pintype "unspecified"))
      (node (ref "U9") (pin "10") (pinfunction "3OE#_10") (pintype "unspecified"))
      (node (ref "U9") (pin "13") (pinfunction "4OE#_13") (pintype "unspecified"))
      (node (ref "U9") (pin "4") (pinfunction "2OE#_4") (pintype "unspecified"))
      (node (ref "U9") (pin "7") (pinfunction "GND_7") (pintype "unspecified"))
    )
    (net (code "7") (name "IO0") (class "Default")
      (node (ref "Q4") (pin "3") (pinfunction "C_3") (pintype "input"))
      (node (ref "R13") (pin "1") (pinfunction "1_1") (pintype "input"))
      (node (ref "U3") (pin "25") (pinfunction "IO0_25") (pintype "unspecified"))
    )
    (net (code "8") (name "IO2") (class "Default")
      (node (ref "R18") (pin "1") (pinfunction "1_1") (pintype "input"))
      (node (ref "R20") (pin "2") (pinfunction "2_2") (pintype "input"))
      (node (ref "U3") (pin "24") (pinfunction "IO2_24") (pintype "unspecified"))
    )
    (net (code "9") (name "IO4") (class "Default")
      (node (ref "R31") (pin "1") (pinfunction "1_1") (pintype "input"))
      (node (ref "U3") (pin "26") (pinfunction "IO4_26") (pintype "unspecified"))
      (node (ref "U8") (pin "2") (pinfunction "RE#_2") (pintype "unspecified"))
      (node (ref "U8") (pin "3") (pinfunction "DE_3") (pintype "unspecified"))
    )
    (net (code "10") (name "IO5") (class "Default")
      (node (ref "U3") (pin "29") (pinfunction "IO5_29") (pintype "unspecified"))
      (node (ref "U9") (pin "2") (pinfunction "1A_2") (pintype "unspecified"))
    )
    (net (code "11") (name "IO13") (class "Default")
      (node (ref "R43") (pin "1") (pinfunction "1_1") (pintype "input"))
      (node (ref "U10") (pin "2") (pinfunction "DQ_2") (pintype "input"))
      (node (ref "U3") (pin "16") (pinfunction "IO13_16") (pintype "unspecified"))
    )
    (net (code "12") (name "IO14") (class "Default")
      (node (ref "R17") (pin "2") (pinfunction "2_2") (pintype "input"))
      (node (ref "U3") (pin "13") (pinfunction "IO14_13") (pintype "unspecified"))
    )
    (net (code "13") (name "IO15") (class "Default")
      (node (ref "R16") (pin "1") (pinfunction "1_1") (pintype "input"))
      (node (ref "TF1") (pin "3") (pinfunction "CMD_3") (pintype "unspecified"))
      (node (ref "U3") (pin "23") (pinfunction "IO15_23") (pintype "unspecified"))
    )
    (net (code "14") (name "IO16") (class "Default")
      (node (ref "R29") (pin "2") (pinfunction "2_2") (pintype "input"))
      (node (ref "U3") (pin "27") (pinfunction "IO16_27") (pintype "unspecified"))
    )
    (net (code "15") (name "IO17") (class "Default")
      (node (ref "R30") (pin "2") (pinfunction "2_2") (pintype "input"))
      (node (ref "U3") (pin "28") (pinfunction "IO17_28") (pintype "unspecified"))
    )
    (net (code "16") (name "IO18") (class "Default")
      (node (ref "U3") (pin "30") (pinfunction "IO18_30") (pintype "unspecified"))
      (node (ref "U9") (pin "5") (pinfunction "2A_5") (pintype "unspecified"))
    )
    (net (code "17") (name "IO19") (class "Default")
      (node (ref "U3") (pin "31") (pinfunction "IO19_31") (pintype "unspecified"))
      (node (ref "U9") (pin "9") (pinfunction "3A_9") (pintype "unspecified"))
    )
    (net (code "18") (name "IO21") (class "Default")
      (node (ref "U3") (pin "33") (pinfunction "IO21_33") (pintype "unspecified"))
      (node (ref "U9") (pin "12") (pinfunction "4A_12") (pintype "unspecified"))
    )
    (net (code "19") (name "IO22") (class "Default")
      (node (ref "C19") (pin "2") (pinfunction "2_2") (pintype "input"))
      (node (ref "R38") (pin "1") (pinfunction "1_1") (pintype "input"))
      (node (ref "SW1") (pin "1") (pinfunction "1_1") (pintype "input"))
      (node (ref "U3") (pin "36") (pinfunction "IO22_36") (pintype "unspecified"))
    )
    (net (code "20") (name "IO23") (class "Default")
      (node (ref "C20") (pin "2") (pinfunction "2_2") (pintype "input"))
      (node (ref "R39") (pin "1") (pinfunction "1_1") (pintype "input"))
      (node (ref "SW2") (pin "1") (pinfunction "1_1") (pintype "input"))
      (node (ref "U3") (pin "37") (pinfunction "IO23_37") (pintype "unspecified"))
    )
    (net (code "21") (name "IO32") (class "Default")
      (node (ref "R21") (pin "2") (pinfunction "2_2") (pintype "input"))
      (node (ref "U3") (pin "8") (pinfunction "IO32_8") (pintype "unspecified"))
    )
    (net (code "22") (name "IO33") (class "Default")
      (node (ref "R23") (pin "2") (pinfunction "2_2") (pintype "input"))
      (node (ref "U3") (pin "9") (pinfunction "IO33_9") (pintype "unspecified"))
    )
    (net (code "23") (name "IO34") (class "Default")
      (node (ref "R25") (pin "2") (pinfunction "2_2") (pintype "input"))
      (node (ref "U3") (pin "6") (pinfunction "IO34_6") (pintype "unspecified"))
    )
    (net (code "24") (name "IO35") (class "Default")
      (node (ref "R27") (pin "2") (pinfunction "2_2") (pintype "input"))
      (node (ref "U3") (pin "7") (pinfunction "IO35_7") (pintype "unspecified"))
    )
    (net (code "25") (name "Net-(C9-Pad1)") (class "Default")
      (node (ref "C9") (pin "1") (pinfunction "1_1") (pintype "input"))
      (node (ref "R8") (pin "2") (pinfunction "2_2") (pintype "input"))
    )
    (net (code "26") (name "Net-(CN3-CC1)") (class "Default")
      (node (ref "CN3") (pin "A5") (pinfunction "CC1_A5") (pintype "input"))
      (node (ref "R4") (pin "2") (pinfunction "2_2") (pintype "input"))
    )
    (net (code "27") (name "Net-(CN3-CC2)") (class "Default")
      (node (ref "CN3") (pin "B5") (pinfunction "CC2_B5") (pintype "input"))
      (node (ref "R3") (pin "2") (pinfunction "2_2") (pintype "input"))
    )
    (net (code "28") (name "Net-(CN4-Pad1)") (class "Default")
      (node (ref "CN4") (pin "1") (pinfunction "1_1") (pintype "unspecified"))
      (node (ref "K2") (pin "3") (pinfunction "3_3") (pintype "unspecified"))
    )
    (net (code "29") (name "Net-(CN4-Pad2)") (class "Default")
      (node (ref "CN4") (pin "2") (pinfunction "2_2") (pintype "unspecified"))
      (node (ref "K2") (pin "2") (pinfunction "2_2") (pintype "unspecified"))
    )
    (net (code "30") (name "Net-(CN5-Pad1)") (class "Default")
      (node (ref "CN5") (pin "1") (pinfunction "1_1") (pintype "unspecified"))
      (node (ref "K3") (pin "3") (pinfunction "3_3") (pintype "unspecified"))
    )
    (net (code "31") (name "Net-(CN5-Pad2)") (class "Default")
      (node (ref "CN5") (pin "2") (pinfunction "2_2") (pintype "unspecified"))
      (node (ref "K3") (pin "2") (pinfunction "2_2") (pintype "unspecified"))
    )
    (net (code "32") (name "Net-(CN6-Pad1)") (class "Default")
      (node (ref "CN6") (pin "1") (pinfunction "1_1") (pintype "unspecified"))
      (node (ref "K4") (pin "3") (pinfunction "3_3") (pintype "unspecified"))
    )
    (net (code "33") (name "Net-(CN6-Pad2)") (class "Default")
      (node (ref "CN6") (pin "2") (pinfunction "2_2") (pintype "unspecified"))
      (node (ref "K4") (pin "2") (pinfunction "2_2") (pintype "unspecified"))
    )
    (net (code "34") (name "Net-(CN9-Pad1)") (class "Default")
      (node (ref "CN9") (pin "1") (pinfunction "1_1") (pintype "unspecified"))
      (node (ref "K1") (pin "3") (pinfunction "3_3") (pintype "unspecified"))
    )
    (net (code "35") (name "Net-(CN9-Pad2)") (class "Default")
      (node (ref "CN9") (pin "2") (pinfunction "2_2") (pintype "unspecified"))
      (node (ref "K1") (pin "2") (pinfunction "2_2") (pintype "unspecified"))
    )
    (net (code "36") (name "Net-(D3-A)") (class "Default")
      (node (ref "D3") (pin "2") (pinfunction "A_2") (pintype "unspecified"))
      (node (ref "LD1") (pin "2") (pinfunction "A_2") (pintype "input"))
      (node (ref "LD2") (pin "2") (pinfunction "A_2") (pintype "input"))
      (node (ref "Q2") (pin "1") (pinfunction "G_1") (pintype "unspecified"))
      (node (ref "R6") (pin "2") (pinfunction "2_2") (pintype "unspecified"))
      (node (ref "U6") (pin "4") (pinfunction "VCC_4") (pintype "unspecified"))
      (node (ref "U6") (pin "8") (pinfunction "CE_8") (pintype "unspecified"))
    )
    (net (code "37") (name "Net-(D4-A)") (class "Default")
      (node (ref "D4") (pin "2") (pinfunction "A_2") (pintype "unspecified"))
      (node (ref "K1") (pin "1") (pinfunction "1_1") (pintype "unspecified"))
      (node (ref "Q5") (pin "3") (pinfunction "C_3") (pintype "input"))
    )
    (net (code "38") (name "Net-(D5-A)") (class "Default")
      (node (ref "D5") (pin "2") (pinfunction "A_2") (pintype "unspecified"))
      (node (ref "K2") (pin "1") (pinfunction "1_1") (pintype "unspecified"))
      (node (ref "Q6") (pin "3") (pinfunction "C_3") (pintype "input"))
    )
    (net (code "39") (name "Net-(D6-A)") (class "Default")
      (node (ref "D6") (pin "2") (pinfunction "A_2") (pintype "unspecified"))
      (node (ref "K3") (pin "1") (pinfunction "1_1") (pintype "unspecified"))
      (node (ref "Q7") (pin "3") (pinfunction "C_3") (pintype "input"))
    )
    (net (code "40") (name "Net-(D7-A)") (class "Default")
      (node (ref "D7") (pin "2") (pinfunction "A_2") (pintype "unspecified"))
      (node (ref "K4") (pin "1") (pinfunction "1_1") (pintype "unspecified"))
      (node (ref "Q8") (pin "3") (pinfunction "C_3") (pintype "input"))
    )
    (net (code "41") (name "Net-(LD1-C)") (class "Default")
      (node (ref "LD1") (pin "1") (pinfunction "C_1") (pintype "input"))
      (node (ref "R5") (pin "2") (pinfunction "2_2") (pintype "input"))
    )
    (net (code "42") (name "Net-(LD2-C)") (class "Default")
      (node (ref "LD2") (pin "1") (pinfunction "C_1") (pintype "input"))
      (node (ref "R2") (pin "2") (pinfunction "2_2") (pintype "input"))
    )
    (net (code "43") (name "Net-(LD3-C)") (class "Default")
      (node (ref "LD3") (pin "1") (pinfunction "C_1") (pintype "input"))
      (node (ref "R42") (pin "1") (pinfunction "1_1") (pintype "input"))
    )
    (net (code "44") (name "Net-(Q3-B)") (class "Default")
      (node (ref "Q3") (pin "1") (pinfunction "B_1") (pintype "input"))
      (node (ref "R10") (pin "1") (pinfunction "1_1") (pintype "input"))
    )
    (net (code "45") (name "Net-(Q3-E)") (class "Default")
      (node (ref "Q3") (pin "2") (pinfunction "E_2") (pintype "input"))
      (node (ref "R11") (pin "2") (pinfunction "2_2") (pintype "input"))
      (node (ref "U4") (pin "14") (pinfunction "RTS#_14") (pintype "unspecified"))
    )
    (net (code "46") (name "Net-(Q4-B)") (class "Default")
      (node (ref "Q4") (pin "1") (pinfunction "B_1") (pintype "input"))
      (node (ref "R11") (pin "1") (pinfunction "1_1") (pintype "input"))
    )
    (net (code "47") (name "Net-(Q4-E)") (class "Default")
      (node (ref "Q4") (pin "2") (pinfunction "E_2") (pintype "input"))
      (node (ref "R10") (pin "2") (pinfunction "2_2") (pintype "input"))
      (node (ref "U4") (pin "13") (pinfunction "DTR#_13") (pintype "unspecified"))
    )
    (net (code "48") (name "Net-(Q5-B)") (class "Default")
      (node (ref "Q5") (pin "1") (pinfunction "B_1") (pintype "input"))
      (node (ref "R21") (pin "1") (pinfunction "1_1") (pintype "input"))
      (node (ref "R22") (pin "2") (pinfunction "2_2") (pintype "input"))
    )
    (net (code "49") (name "Net-(Q6-B)") (class "Default")
      (node (ref "Q6") (pin "1") (pinfunction "B_1") (pintype "input"))
      (node (ref "R23") (pin "1") (pinfunction "1_1") (pintype "input"))
      (node (ref "R24") (pin "2") (pinfunction "2_2") (pintype "input"))
    )
    (net (code "50") (name "Net-(Q7-B)") (class "Default")
      (node (ref "Q7") (pin "1") (pinfunction "B_1") (pintype "input"))
      (node (ref "R25") (pin "1") (pinfunction "1_1") (pintype "input"))
      (node (ref "R26") (pin "2") (pinfunction "2_2") (pintype "input"))
    )
    (net (code "51") (name "Net-(Q8-B)") (class "Default")
      (node (ref "Q8") (pin "1") (pinfunction "B_1") (pintype "input"))
      (node (ref "R27") (pin "1") (pinfunction "1_1") (pintype "input"))
      (node (ref "R28") (pin "2") (pinfunction "2_2") (pintype "input"))
    )
    (net (code "52") (name "Net-(R32-Pad2)") (class "Default")
      (node (ref "R32") (pin "2") (pinfunction "2_2") (pintype "input"))
      (node (ref "R33") (pin "2") (pinfunction "2_2") (pintype "input"))
    )
    (net (code "53") (name "Net-(TF1-CD{slash}DAT3)") (class "Default")
      (node (ref "R15") (pin "1") (pinfunction "1_1") (pintype "input"))
      (node (ref "TF1") (pin "2") (pinfunction "CD/DAT3_2") (pintype "unspecified"))
    )
    (net (code "54") (name "Net-(TF1-CLK)") (class "Default")
      (node (ref "R17") (pin "1") (pinfunction "1_1") (pintype "input"))
      (node (ref "TF1") (pin "5") (pinfunction "CLK_5") (pintype "unspecified"))
    )
    (net (code "55") (name "Net-(TF1-DAT0)") (class "Default")
      (node (ref "R20") (pin "1") (pinfunction "1_1") (pintype "input"))
      (node (ref "TF1") (pin "7") (pinfunction "DAT0_7") (pintype "unspecified"))
    )
    (net (code "56") (name "Net-(TF1-DAT1)") (class "Default")
      (node (ref "R19") (pin "1") (pinfunction "1_1") (pintype "input"))
      (node (ref "TF1") (pin "8") (pinfunction "DAT1_8") (pintype "unspecified"))
    )
    (net (code "57") (name "Net-(TF1-DAT2)") (class "Default")
      (node (ref "R14") (pin "1") (pinfunction "1_1") (pintype "input"))
      (node (ref "TF1") (pin "1") (pinfunction "DAT2_1") (pintype "unspecified"))
    )
    (net (code "58") (name "Net-(TF1-VDD)") (class "Default")
      (node (ref "C15") (pin "1") (pinfunction "1_1") (pintype "input"))
      (node (ref "FB1") (pin "2") (pinfunction "2_2") (pintype "unspecified"))
      (node (ref "TF1") (pin "4") (pinfunction "VDD_4") (pintype "unspecified"))
    )
    (net (code "59") (name "Net-(U6-CHRG#)") (class "Default")
      (node (ref "R2") (pin "1") (pinfunction "1_1") (pintype "input"))
      (node (ref "U6") (pin "7") (pinfunction "CHRG#_7") (pintype "unspecified"))
    )
    (net (code "60") (name "Net-(U6-PROG)") (class "Default")
      (node (ref "R7") (pin "1") (pinfunction "1_1") (pintype "input"))
      (node (ref "U6") (pin "2") (pinfunction "PROG_2") (pintype "unspecified"))
    )
    (net (code "61") (name "Net-(U6-STDBY#)") (class "Default")
      (node (ref "R5") (pin "1") (pinfunction "1_1") (pintype "input"))
      (node (ref "U6") (pin "6") (pinfunction "STDBY#_6") (pintype "unspecified"))
    )
    (net (code "62") (name "Net-(U7-FB)") (class "Default")
      (node (ref "C9") (pin "2") (pinfunction "2_2") (pintype "input"))
      (node (ref "R8") (pin "1") (pinfunction "1_1") (pintype "input"))
      (node (ref "R9") (pin "2") (pinfunction "2_2") (pintype "input"))
      (node (ref "U7") (pin "5") (pinfunction "FB_5") (pintype "input"))
    )
    (net (code "63") (name "Net-(U7-SW)") (class "Default")
      (node (ref "L1") (pin "1") (pinfunction "1_1") (pintype "unspecified"))
      (node (ref "U7") (pin "3") (pinfunction "SW_3") (pintype "input"))
    )
    (net (code "64") (name "Net-(U8-DI)") (class "Default")
      (node (ref "R30") (pin "1") (pinfunction "1_1") (pintype "input"))
      (node (ref "U8") (pin "4") (pinfunction "DI_4") (pintype "unspecified"))
    )
    (net (code "65") (name "Net-(U8-R0)") (class "Default")
      (node (ref "R29") (pin "1") (pinfunction "1_1") (pintype "input"))
      (node (ref "U8") (pin "1") (pinfunction "R0_1") (pintype "unspecified"))
    )
    (net (code "66") (name "Net-(U9-1Y)") (class "Default")
      (node (ref "CN8") (pin "1") (pinfunction "1_1") (pintype "unspecified"))
      (node (ref "U9") (pin "3") (pinfunction "1Y_3") (pintype "unspecified"))
    )
    (net (code "67") (name "Net-(U9-2Y)") (class "Default")
      (node (ref "CN8") (pin "3") (pinfunction "3_3") (pintype "unspecified"))
      (node (ref "U9") (pin "6") (pinfunction "2Y_6") (pintype "unspecified"))
    )
    (net (code "68") (name "Net-(U9-3Y)") (class "Default")
      (node (ref "CN8") (pin "5") (pinfunction "5_5") (pintype "unspecified"))
      (node (ref "U9") (pin "8") (pinfunction "3Y_8") (pintype "unspecified"))
    )
    (net (code "69") (name "Net-(U9-4Y)") (class "Default")
      (node (ref "CN8") (pin "7") (pinfunction "7_7") (pintype "unspecified"))
      (node (ref "U9") (pin "11") (pinfunction "4Y_11") (pintype "unspecified"))
    )
    (net (code "70") (name "Net-(U9-VCC)") (class "Default")
      (node (ref "C21") (pin "2") (pinfunction "2_2") (pintype "input"))
      (node (ref "C22") (pin "2") (pinfunction "2_2") (pintype "input"))
      (node (ref "R40") (pin "1") (pinfunction "1_1") (pintype "input"))
      (node (ref "R41") (pin "1") (pinfunction "1_1") (pintype "input"))
      (node (ref "U9") (pin "14") (pinfunction "VCC_14") (pintype "unspecified"))
    )
    (net (code "71") (name "RS485+") (class "Default")
      (node (ref "CN10") (pin "2") (pinfunction "2_2") (pintype "unspecified"))
      (node (ref "R33") (pin "1") (pinfunction "1_1") (pintype "input"))
      (node (ref "U8") (pin "6") (pinfunction "A_6") (pintype "unspecified"))
    )
    (net (code "72") (name "RS485-") (class "Default")
      (node (ref "CN10") (pin "1") (pinfunction "1_1") (pintype "unspecified"))
      (node (ref "R32") (pin "1") (pinfunction "1_1") (pintype "input"))
      (node (ref "U8") (pin "7") (pinfunction "B_7") (pintype "unspecified"))
    )
    (net (code "73") (name "RXD0") (class "Default")
      (node (ref "U3") (pin "34") (pinfunction "RXD0_34") (pintype "unspecified"))
      (node (ref "U4") (pin "2") (pinfunction "TXD_2") (pintype "unspecified"))
    )
    (net (code "74") (name "TXD0") (class "Default")
      (node (ref "U3") (pin "35") (pinfunction "TXD0_35") (pintype "unspecified"))
      (node (ref "U4") (pin "3") (pinfunction "RXD_3") (pintype "unspecified"))
    )
    (net (code "75") (name "USR_LED") (class "Default")
      (node (ref "R42") (pin "2") (pinfunction "2_2") (pintype "input"))
      (node (ref "U3") (pin "14") (pinfunction "IO12_14") (pintype "unspecified"))
    )
    (net (code "76") (name "VBAT") (class "Default")
      (node (ref "C5") (pin "2") (pinfunction "2_2") (pintype "input"))
      (node (ref "C6") (pin "2") (pinfunction "2_2") (pintype "input"))
      (node (ref "CN2") (pin "1") (pinfunction "1_1") (pintype "unspecified"))
      (node (ref "Q2") (pin "3") (pinfunction "D_3") (pintype "unspecified"))
      (node (ref "R36") (pin "2") (pinfunction "2_2") (pintype "input"))
      (node (ref "U6") (pin "5") (pinfunction "BAT_5") (pintype "unspecified"))
    )
    (net (code "77") (name "VBUS") (class "Default")
      (node (ref "CN3") (pin "A4") (pinfunction "VBUS_A4") (pintype "input"))
      (node (ref "CN3") (pin "A9") (pinfunction "VBUS_A9") (pintype "input"))
      (node (ref "CN3") (pin "B4") (pinfunction "VBUS_B4") (pintype "input"))
      (node (ref "CN3") (pin "B9") (pinfunction "VBUS_B9") (pintype "input"))
      (node (ref "Q1") (pin "3") (pinfunction "D_3") (pintype "unspecified"))
    )
    (net (code "78") (name "VDC") (class "Default")
      (node (ref "C7") (pin "2") (pinfunction "2_2") (pintype "input"))
      (node (ref "C8") (pin "2") (pinfunction "2_2") (pintype "input"))
      (node (ref "D3") (pin "1") (pinfunction "C_1") (pintype "unspecified"))
      (node (ref "Q2") (pin "2") (pinfunction "S_2") (pintype "unspecified"))
      (node (ref "U7") (pin "1") (pinfunction "EN_1") (pintype "input"))
    )
    (net (code "79") (name "VDD") (class "Default")
      (node (ref "C10") (pin "2") (pinfunction "2_2") (pintype "input"))
      (node (ref "C11") (pin "2") (pinfunction "2_2") (pintype "input"))
      (node (ref "C12") (pin "1") (pinfunction "1_1") (pintype "input"))
      (node (ref "C13") (pin "2") (pinfunction "2_2") (pintype "input"))
      (node (ref "C16") (pin "1") (pinfunction "1_1") (pintype "input"))
      (node (ref "C23") (pin "1") (pinfunction "1_1") (pintype "input"))
      (node (ref "CN8") (pin "6") (pinfunction "6_6") (pintype "unspecified"))
      (node (ref "FB1") (pin "1") (pinfunction "1_1") (pintype "unspecified"))
      (node (ref "L1") (pin "2") (pinfunction "2_2") (pintype "unspecified"))
      (node (ref "LD3") (pin "2") (pinfunction "A_2") (pintype "input"))
      (node (ref "R12") (pin "2") (pinfunction "2_2") (pintype "input"))
      (node (ref "R13") (pin "2") (pinfunction "2_2") (pintype "input"))
      (node (ref "R14") (pin "2") (pinfunction "2_2") (pintype "input"))
      (node (ref "R15") (pin "2") (pinfunction "2_2") (pintype "input"))
      (node (ref "R16") (pin "2") (pinfunction "2_2") (pintype "input"))
      (node (ref "R18") (pin "2") (pinfunction "2_2") (pintype "input"))
      (node (ref "R19") (pin "2") (pinfunction "2_2") (pintype "input"))
      (node (ref "R38") (pin "2") (pinfunction "2_2") (pintype "input"))
      (node (ref "R39") (pin "2") (pinfunction "2_2") (pintype "input"))
      (node (ref "R41") (pin "2") (pinfunction "2_2") (pintype "input"))
      (node (ref "R43") (pin "2") (pinfunction "2_2") (pintype "input"))
      (node (ref "U10") (pin "3") (pinfunction "VDD_3") (pintype "input"))
      (node (ref "U3") (pin "2") (pinfunction "3V3_2") (pintype "unspecified"))
      (node (ref "U4") (pin "16") (pinfunction "VCC_16") (pintype "unspecified"))
      (node (ref "U4") (pin "4") (pinfunction "V3_4") (pintype "unspecified"))
      (node (ref "U8") (pin "8") (pinfunction "VCC_8") (pintype "unspecified"))
    )
    (net (code "80") (name "VEXT") (class "Default")
      (node (ref "C1") (pin "1") (pinfunction "1_1") (pintype "input"))
      (node (ref "C2") (pin "1") (pinfunction "1_1") (pintype "input"))
      (node (ref "C3") (pin "2") (pinfunction "2_2") (pintype "input"))
      (node (ref "C4") (pin "2") (pinfunction "2_2") (pintype "input"))
      (node (ref "CN8") (pin "2") (pinfunction "2_2") (pintype "unspecified"))
      (node (ref "D1") (pin "1") (pinfunction "C_1") (pintype "unspecified"))
      (node (ref "D2") (pin "1") (pinfunction "1_1") (pintype "unspecified"))
      (node (ref "D4") (pin "1") (pinfunction "C_1") (pintype "unspecified"))
      (node (ref "D5") (pin "1") (pinfunction "C_1") (pintype "unspecified"))
      (node (ref "D6") (pin "1") (pinfunction "C_1") (pintype "unspecified"))
      (node (ref "D7") (pin "1") (pinfunction "C_1") (pintype "unspecified"))
      (node (ref "K1") (pin "4") (pinfunction "4_4") (pintype "unspecified"))
      (node (ref "K2") (pin "4") (pinfunction "4_4") (pintype "unspecified"))
      (node (ref "K3") (pin "4") (pinfunction "4_4") (pintype "unspecified"))
      (node (ref "K4") (pin "4") (pinfunction "4_4") (pintype "unspecified"))
      (node (ref "Q1") (pin "2") (pinfunction "S_2") (pintype "unspecified"))
      (node (ref "R34") (pin "1") (pinfunction "1_1") (pintype "input"))
      (node (ref "R40") (pin "2") (pinfunction "2_2") (pintype "input"))
      (node (ref "R6") (pin "1") (pinfunction "1_1") (pintype "unspecified"))
    )
    (net (code "81") (name "V_EXT") (class "Default")
      (node (ref "CN1") (pin "1") (pinfunction "1_1") (pintype "unspecified"))
      (node (ref "D1") (pin "2") (pinfunction "A_2") (pintype "unspecified"))
      (node (ref "DC1") (pin "1") (pinfunction "4_1") (pintype "input"))
      (node (ref "Q1") (pin "1") (pinfunction "G_1") (pintype "unspecified"))
      (node (ref "R1") (pin "2") (pinfunction "2_2") (pintype "input"))
    )
    (net (code "82") (name "unconnected-(CN3-SBUS1-PadA8)") (class "Default")
      (node (ref "CN3") (pin "A8") (pinfunction "SBUS1_A8") (pintype "input+no_connect"))
    )
    (net (code "83") (name "unconnected-(CN3-SBUS2-PadB8)") (class "Default")
      (node (ref "CN3") (pin "B8") (pinfunction "SBUS2_B8") (pintype "input+no_connect"))
    )
    (net (code "84") (name "unconnected-(TF1-CD-Pad9)") (class "Default")
      (node (ref "TF1") (pin "9") (pinfunction "CD_9") (pintype "unspecified+no_connect"))
    )
    (net (code "85") (name "unconnected-(U3-CLK-Pad20)") (class "Default")
      (node (ref "U3") (pin "20") (pinfunction "CLK_20") (pintype "unspecified+no_connect"))
    )
    (net (code "86") (name "unconnected-(U3-CMD-Pad19)") (class "Default")
      (node (ref "U3") (pin "19") (pinfunction "CMD_19") (pintype "unspecified+no_connect"))
    )
    (net (code "87") (name "unconnected-(U3-IO27-Pad12)") (class "Default")
      (node (ref "U3") (pin "12") (pinfunction "IO27_12") (pintype "unspecified+no_connect"))
    )
    (net (code "88") (name "unconnected-(U3-NC-Pad32)") (class "Default")
      (node (ref "U3") (pin "32") (pinfunction "NC_32") (pintype "unspecified+no_connect"))
    )
    (net (code "89") (name "unconnected-(U3-SD0-Pad21)") (class "Default")
      (node (ref "U3") (pin "21") (pinfunction "SD0_21") (pintype "unspecified+no_connect"))
    )
    (net (code "90") (name "unconnected-(U3-SD1-Pad22)") (class "Default")
      (node (ref "U3") (pin "22") (pinfunction "SD1_22") (pintype "unspecified+no_connect"))
    )
    (net (code "91") (name "unconnected-(U3-SD2-Pad17)") (class "Default")
      (node (ref "U3") (pin "17") (pinfunction "SD2_17") (pintype "unspecified+no_connect"))
    )
    (net (code "92") (name "unconnected-(U3-SD3-Pad18)") (class "Default")
      (node (ref "U3") (pin "18") (pinfunction "SD3_18") (pintype "unspecified+no_connect"))
    )
    (net (code "93") (name "unconnected-(U3-SENSOR_VN-Pad5)") (class "Default")
      (node (ref "U3") (pin "5") (pinfunction "SENSOR_VN_5") (pintype "unspecified+no_connect"))
    )
    (net (code "94") (name "unconnected-(U3-SENSOR_VP-Pad4)") (class "Default")
      (node (ref "U3") (pin "4") (pinfunction "SENSOR_VP_4") (pintype "unspecified+no_connect"))
    )
    (net (code "95") (name "unconnected-(U4-CTS#-Pad9)") (class "Default")
      (node (ref "U4") (pin "9") (pinfunction "CTS#_9") (pintype "unspecified+no_connect"))
    )
    (net (code "96") (name "unconnected-(U4-DCD#-Pad12)") (class "Default")
      (node (ref "U4") (pin "12") (pinfunction "DCD#_12") (pintype "unspecified+no_connect"))
    )
    (net (code "97") (name "unconnected-(U4-DSR#-Pad10)") (class "Default")
      (node (ref "U4") (pin "10") (pinfunction "DSR#_10") (pintype "unspecified+no_connect"))
    )
    (net (code "98") (name "unconnected-(U4-NC.-Pad7)") (class "Default")
      (node (ref "U4") (pin "7") (pinfunction "NC._7") (pintype "unspecified+no_connect"))
    )
    (net (code "99") (name "unconnected-(U4-OUT#-Pad8)") (class "Default")
      (node (ref "U4") (pin "8") (pinfunction "OUT#_8") (pintype "unspecified+no_connect"))
    )
    (net (code "100") (name "unconnected-(U4-R232-Pad15)") (class "Default")
      (node (ref "U4") (pin "15") (pinfunction "R232_15") (pintype "unspecified+no_connect"))
    )
    (net (code "101") (name "unconnected-(U4-RI#-Pad11)") (class "Default")
      (node (ref "U4") (pin "11") (pinfunction "RI#_11") (pintype "unspecified+no_connect"))
    )
    (net (code "102") (name "unconnected-(U7-VIN-Pad4)") (class "Default")
      (node (ref "U7") (pin "4") (pinfunction "VIN_4") (pintype "input"))
    )
  )
)
